# IR4427.net
KiCad netlist of a schematic drawn in EAGLE
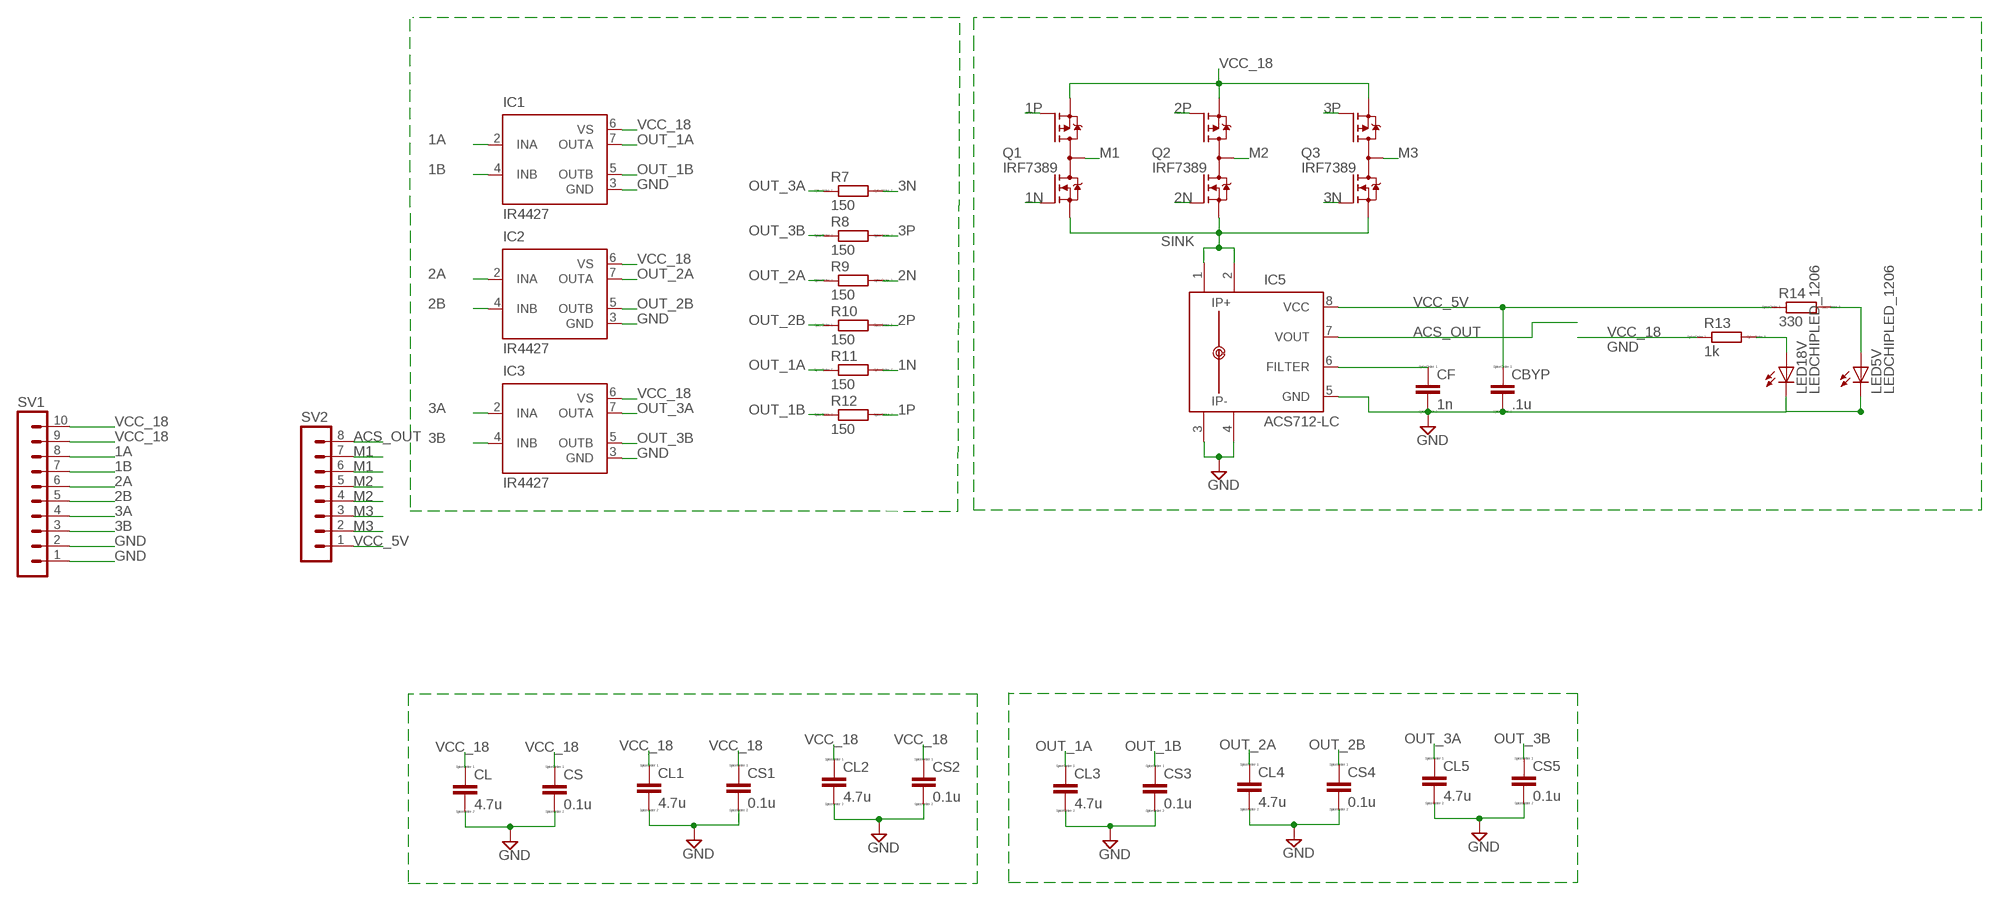
[diagram p0: schematic, sheet 1]

(export (version "E")
  (design (tool "Eeschema 10.0.6"))
  (components
    (comp (ref "CBYP")
      (value ".1u")
      (footprint "eagle-import:C1206")
      (libsource (lib "eagle-import") (part "CC1206"))
    )
    (comp (ref "CF")
      (value "1n")
      (footprint "eagle-import:C1206")
      (libsource (lib "eagle-import") (part "CC1206"))
    )
    (comp (ref "CL")
      (value "4.7u")
      (footprint "eagle-import:C1206")
      (libsource (lib "eagle-import") (part "CC1206"))
    )
    (comp (ref "CL1")
      (value "4.7u")
      (footprint "eagle-import:C1206")
      (libsource (lib "eagle-import") (part "CC1206"))
    )
    (comp (ref "CL2")
      (value "4.7u")
      (footprint "eagle-import:C1206")
      (libsource (lib "eagle-import") (part "CC1206"))
    )
    (comp (ref "CL3")
      (value "4.7u")
      (footprint "eagle-import:C1206")
      (libsource (lib "eagle-import") (part "CC1206"))
    )
    (comp (ref "CL4")
      (value "4.7u")
      (footprint "eagle-import:C1206")
      (libsource (lib "eagle-import") (part "CC1206"))
    )
    (comp (ref "CL5")
      (value "4.7u")
      (footprint "eagle-import:C1206")
      (libsource (lib "eagle-import") (part "CC1206"))
    )
    (comp (ref "CS")
      (value "0.1u")
      (footprint "eagle-import:C1206")
      (libsource (lib "eagle-import") (part "CC1206"))
    )
    (comp (ref "CS1")
      (value "0.1u")
      (footprint "eagle-import:C1206")
      (libsource (lib "eagle-import") (part "CC1206"))
    )
    (comp (ref "CS2")
      (value "0.1u")
      (footprint "eagle-import:C1206")
      (libsource (lib "eagle-import") (part "CC1206"))
    )
    (comp (ref "CS3")
      (value "0.1u")
      (footprint "eagle-import:C1206")
      (libsource (lib "eagle-import") (part "CC1206"))
    )
    (comp (ref "CS4")
      (value "0.1u")
      (footprint "eagle-import:C1206")
      (libsource (lib "eagle-import") (part "CC1206"))
    )
    (comp (ref "CS5")
      (value "0.1u")
      (footprint "eagle-import:C1206")
      (libsource (lib "eagle-import") (part "CC1206"))
    )
    (comp (ref "IC1")
      (value "IR4427")
      (footprint "eagle-import:DIL08")
      (fields (field (name "MF") "INTERNATIONAL RECTIFIER(IR)"))
      (libsource (lib "eagle-import") (part "IR4427"))
    )
    (comp (ref "IC2")
      (value "IR4427")
      (footprint "eagle-import:DIL08")
      (fields (field (name "MF") "INTERNATIONAL RECTIFIER(IR)"))
      (libsource (lib "eagle-import") (part "IR4427"))
    )
    (comp (ref "IC3")
      (value "IR4427")
      (footprint "eagle-import:DIL08")
      (fields (field (name "MF") "INTERNATIONAL RECTIFIER(IR)"))
      (libsource (lib "eagle-import") (part "IR4427"))
    )
    (comp (ref "IC5")
      (value "ACS712-LC")
      (footprint "eagle-import:SOIC8")
      (libsource (lib "eagle-import") (part "ACS712-LC"))
    )
    (comp (ref "LED5V")
      (value "LEDCHIPLED_1206")
      (footprint "eagle-import:CHIPLED_1206")
      (libsource (lib "eagle-import") (part "LEDCHIPLED_1206"))
    )
    (comp (ref "LED18V")
      (value "LEDCHIPLED_1206")
      (footprint "eagle-import:CHIPLED_1206")
      (libsource (lib "eagle-import") (part "LEDCHIPLED_1206"))
    )
    (comp (ref "Q1")
      (value "IRF7389")
      (footprint "eagle-import:SO08-IRF")
      (libsource (lib "eagle-import") (part "IRF7389"))
    )
    (comp (ref "Q2")
      (value "IRF7389")
      (footprint "eagle-import:SO08-IRF")
      (libsource (lib "eagle-import") (part "IRF7389"))
    )
    (comp (ref "Q3")
      (value "IRF7389")
      (footprint "eagle-import:SO08-IRF")
      (libsource (lib "eagle-import") (part "IRF7389"))
    )
    (comp (ref "R7")
      (value "150")
      (footprint "eagle-import:R1206")
      (libsource (lib "eagle-import") (part "RR1206"))
    )
    (comp (ref "R8")
      (value "150")
      (footprint "eagle-import:R1206")
      (libsource (lib "eagle-import") (part "RR1206"))
    )
    (comp (ref "R9")
      (value "150")
      (footprint "eagle-import:R1206")
      (libsource (lib "eagle-import") (part "RR1206"))
    )
    (comp (ref "R10")
      (value "150")
      (footprint "eagle-import:R1206")
      (libsource (lib "eagle-import") (part "RR1206"))
    )
    (comp (ref "R11")
      (value "150")
      (footprint "eagle-import:R1206")
      (libsource (lib "eagle-import") (part "RR1206"))
    )
    (comp (ref "R12")
      (value "150")
      (footprint "eagle-import:R1206")
      (libsource (lib "eagle-import") (part "RR1206"))
    )
    (comp (ref "R13")
      (value "1k")
      (footprint "eagle-import:R1206")
      (libsource (lib "eagle-import") (part "RR1206"))
    )
    (comp (ref "R14")
      (value "330")
      (footprint "eagle-import:R1206")
      (libsource (lib "eagle-import") (part "RR1206"))
    )
    (comp (ref "SV1")
      (value "MA10-1")
      (footprint "eagle-import:MA10-1")
      (libsource (lib "eagle-import") (part "MA10-1"))
    )
    (comp (ref "SV2")
      (value "MA08-1")
      (footprint "eagle-import:MA08-1")
      (libsource (lib "eagle-import") (part "MA08-1"))
    )
  )
  (nets
    (net (code "1") (name "/1A") (class "Default")
      (node (ref "IC1") (pin "2") (pinfunction "INA_2") (pintype "input"))
      (node (ref "SV1") (pin "8") (pinfunction "8_8") (pintype "passive"))
    )
    (net (code "2") (name "/1B") (class "Default")
      (node (ref "IC1") (pin "4") (pinfunction "INB_4") (pintype "input"))
      (node (ref "SV1") (pin "7") (pinfunction "7_7") (pintype "passive"))
    )
    (net (code "3") (name "/1N") (class "Default")
      (node (ref "Q1") (pin "2") (pinfunction "N-G_2") (pintype "passive"))
      (node (ref "R11") (pin "2") (pinfunction "2_2") (pintype "passive"))
    )
    (net (code "4") (name "/1P") (class "Default")
      (node (ref "Q1") (pin "4") (pinfunction "P-G_4") (pintype "passive"))
      (node (ref "R12") (pin "2") (pinfunction "2_2") (pintype "passive"))
    )
    (net (code "5") (name "/2A") (class "Default")
      (node (ref "IC2") (pin "2") (pinfunction "INA_2") (pintype "input"))
      (node (ref "SV1") (pin "6") (pinfunction "6_6") (pintype "passive"))
    )
    (net (code "6") (name "/2B") (class "Default")
      (node (ref "IC2") (pin "4") (pinfunction "INB_4") (pintype "input"))
      (node (ref "SV1") (pin "5") (pinfunction "5_5") (pintype "passive"))
    )
    (net (code "7") (name "/2N") (class "Default")
      (node (ref "Q2") (pin "2") (pinfunction "N-G_2") (pintype "passive"))
      (node (ref "R9") (pin "2") (pinfunction "2_2") (pintype "passive"))
    )
    (net (code "8") (name "/2P") (class "Default")
      (node (ref "Q2") (pin "4") (pinfunction "P-G_4") (pintype "passive"))
      (node (ref "R10") (pin "2") (pinfunction "2_2") (pintype "passive"))
    )
    (net (code "9") (name "/3A") (class "Default")
      (node (ref "IC3") (pin "2") (pinfunction "INA_2") (pintype "input"))
      (node (ref "SV1") (pin "4") (pinfunction "4_4") (pintype "passive"))
    )
    (net (code "10") (name "/3B") (class "Default")
      (node (ref "IC3") (pin "4") (pinfunction "INB_4") (pintype "input"))
      (node (ref "SV1") (pin "3") (pinfunction "3_3") (pintype "passive"))
    )
    (net (code "11") (name "/3N") (class "Default")
      (node (ref "Q3") (pin "2") (pinfunction "N-G_2") (pintype "passive"))
      (node (ref "R7") (pin "2") (pinfunction "2_2") (pintype "passive"))
    )
    (net (code "12") (name "/3P") (class "Default")
      (node (ref "Q3") (pin "4") (pinfunction "P-G_4") (pintype "passive"))
      (node (ref "R8") (pin "2") (pinfunction "2_2") (pintype "passive"))
    )
    (net (code "13") (name "/ACS_OUT") (class "Default")
      (node (ref "IC5") (pin "7") (pinfunction "VOUT_7") (pintype "output"))
      (node (ref "SV2") (pin "8") (pinfunction "8_8") (pintype "passive"))
    )
    (net (code "14") (name "/M1") (class "Default")
      (node (ref "Q1") (pin "5") (pinfunction "D_5") (pintype "passive"))
      (node (ref "Q1") (pin "6") (pinfunction "D_6") (pintype "passive"))
      (node (ref "Q1") (pin "7") (pinfunction "D_7") (pintype "passive"))
      (node (ref "Q1") (pin "8") (pinfunction "D_8") (pintype "passive"))
      (node (ref "SV2") (pin "6") (pinfunction "6_6") (pintype "passive"))
      (node (ref "SV2") (pin "7") (pinfunction "7_7") (pintype "passive"))
    )
    (net (code "15") (name "/M2") (class "Default")
      (node (ref "Q2") (pin "5") (pinfunction "D_5") (pintype "passive"))
      (node (ref "Q2") (pin "6") (pinfunction "D_6") (pintype "passive"))
      (node (ref "Q2") (pin "7") (pinfunction "D_7") (pintype "passive"))
      (node (ref "Q2") (pin "8") (pinfunction "D_8") (pintype "passive"))
      (node (ref "SV2") (pin "4") (pinfunction "4_4") (pintype "passive"))
      (node (ref "SV2") (pin "5") (pinfunction "5_5") (pintype "passive"))
    )
    (net (code "16") (name "/M3") (class "Default")
      (node (ref "Q3") (pin "5") (pinfunction "D_5") (pintype "passive"))
      (node (ref "Q3") (pin "6") (pinfunction "D_6") (pintype "passive"))
      (node (ref "Q3") (pin "7") (pinfunction "D_7") (pintype "passive"))
      (node (ref "Q3") (pin "8") (pinfunction "D_8") (pintype "passive"))
      (node (ref "SV2") (pin "2") (pinfunction "2_2") (pintype "passive"))
      (node (ref "SV2") (pin "3") (pinfunction "3_3") (pintype "passive"))
    )
    (net (code "17") (name "/OUT_1A") (class "Default")
      (node (ref "CL3") (pin "1") (pinfunction "1_1") (pintype "passive"))
      (node (ref "IC1") (pin "7") (pinfunction "OUTA_7") (pintype "output"))
      (node (ref "R11") (pin "1") (pinfunction "1_1") (pintype "passive"))
    )
    (net (code "18") (name "/OUT_1B") (class "Default")
      (node (ref "CS3") (pin "1") (pinfunction "1_1") (pintype "passive"))
      (node (ref "IC1") (pin "5") (pinfunction "OUTB_5") (pintype "output"))
      (node (ref "R12") (pin "1") (pinfunction "1_1") (pintype "passive"))
    )
    (net (code "19") (name "/OUT_2A") (class "Default")
      (node (ref "CL4") (pin "1") (pinfunction "1_1") (pintype "passive"))
      (node (ref "IC2") (pin "7") (pinfunction "OUTA_7") (pintype "output"))
      (node (ref "R9") (pin "1") (pinfunction "1_1") (pintype "passive"))
    )
    (net (code "20") (name "/OUT_2B") (class "Default")
      (node (ref "CS4") (pin "1") (pinfunction "1_1") (pintype "passive"))
      (node (ref "IC2") (pin "5") (pinfunction "OUTB_5") (pintype "output"))
      (node (ref "R10") (pin "1") (pinfunction "1_1") (pintype "passive"))
    )
    (net (code "21") (name "/OUT_3A") (class "Default")
      (node (ref "CL5") (pin "1") (pinfunction "1_1") (pintype "passive"))
      (node (ref "IC3") (pin "7") (pinfunction "OUTA_7") (pintype "output"))
      (node (ref "R7") (pin "1") (pinfunction "1_1") (pintype "passive"))
    )
    (net (code "22") (name "/OUT_3B") (class "Default")
      (node (ref "CS5") (pin "1") (pinfunction "1_1") (pintype "passive"))
      (node (ref "IC3") (pin "5") (pinfunction "OUTB_5") (pintype "output"))
      (node (ref "R8") (pin "1") (pinfunction "1_1") (pintype "passive"))
    )
    (net (code "23") (name "/SINK") (class "Default")
      (node (ref "IC5") (pin "1") (pinfunction "IP+_1") (pintype "passive"))
      (node (ref "IC5") (pin "2") (pinfunction "IP+1_2") (pintype "passive"))
      (node (ref "Q1") (pin "1") (pinfunction "N-S_1") (pintype "passive"))
      (node (ref "Q2") (pin "1") (pinfunction "N-S_1") (pintype "passive"))
      (node (ref "Q3") (pin "1") (pinfunction "N-S_1") (pintype "passive"))
    )
    (net (code "24") (name "/VCC_5V") (class "Default")
      (node (ref "CBYP") (pin "1") (pinfunction "1_1") (pintype "passive"))
      (node (ref "IC5") (pin "8") (pinfunction "VCC_8") (pintype "power_in"))
      (node (ref "R14") (pin "1") (pinfunction "1_1") (pintype "passive"))
      (node (ref "SV2") (pin "1") (pinfunction "1_1") (pintype "passive"))
    )
    (net (code "25") (name "/VCC_18") (class "Default")
      (node (ref "CL") (pin "1") (pinfunction "1_1") (pintype "passive"))
      (node (ref "CL1") (pin "1") (pinfunction "1_1") (pintype "passive"))
      (node (ref "CL2") (pin "1") (pinfunction "1_1") (pintype "passive"))
      (node (ref "CS") (pin "1") (pinfunction "1_1") (pintype "passive"))
      (node (ref "CS1") (pin "1") (pinfunction "1_1") (pintype "passive"))
      (node (ref "CS2") (pin "1") (pinfunction "1_1") (pintype "passive"))
      (node (ref "IC1") (pin "6") (pinfunction "VS_6") (pintype "power_in"))
      (node (ref "IC2") (pin "6") (pinfunction "VS_6") (pintype "power_in"))
      (node (ref "IC3") (pin "6") (pinfunction "VS_6") (pintype "power_in"))
      (node (ref "Q1") (pin "3") (pinfunction "P-S_3") (pintype "passive"))
      (node (ref "Q2") (pin "3") (pinfunction "P-S_3") (pintype "passive"))
      (node (ref "Q3") (pin "3") (pinfunction "P-S_3") (pintype "passive"))
      (node (ref "R13") (pin "1") (pinfunction "1_1") (pintype "passive"))
      (node (ref "SV1") (pin "10") (pinfunction "10_10") (pintype "passive"))
      (node (ref "SV1") (pin "9") (pinfunction "9_9") (pintype "passive"))
    )
    (net (code "26") (name "GND") (class "Default")
      (node (ref "CBYP") (pin "2") (pinfunction "2_2") (pintype "passive"))
      (node (ref "CF") (pin "2") (pinfunction "2_2") (pintype "passive"))
      (node (ref "CL") (pin "2") (pinfunction "2_2") (pintype "passive"))
      (node (ref "CL1") (pin "2") (pinfunction "2_2") (pintype "passive"))
      (node (ref "CL2") (pin "2") (pinfunction "2_2") (pintype "passive"))
      (node (ref "CL3") (pin "2") (pinfunction "2_2") (pintype "passive"))
      (node (ref "CL4") (pin "2") (pinfunction "2_2") (pintype "passive"))
      (node (ref "CL5") (pin "2") (pinfunction "2_2") (pintype "passive"))
      (node (ref "CS") (pin "2") (pinfunction "2_2") (pintype "passive"))
      (node (ref "CS1") (pin "2") (pinfunction "2_2") (pintype "passive"))
      (node (ref "CS2") (pin "2") (pinfunction "2_2") (pintype "passive"))
      (node (ref "CS3") (pin "2") (pinfunction "2_2") (pintype "passive"))
      (node (ref "CS4") (pin "2") (pinfunction "2_2") (pintype "passive"))
      (node (ref "CS5") (pin "2") (pinfunction "2_2") (pintype "passive"))
      (node (ref "IC1") (pin "3") (pinfunction "GND_3") (pintype "power_in"))
      (node (ref "IC2") (pin "3") (pinfunction "GND_3") (pintype "power_in"))
      (node (ref "IC3") (pin "3") (pinfunction "GND_3") (pintype "power_in"))
      (node (ref "IC5") (pin "3") (pinfunction "IP-_3") (pintype "passive"))
      (node (ref "IC5") (pin "4") (pinfunction "IP-1_4") (pintype "passive"))
      (node (ref "IC5") (pin "5") (pinfunction "GND_5") (pintype "power_in"))
      (node (ref "LED18V") (pin "C") (pinfunction "C_C") (pintype "passive"))
      (node (ref "LED5V") (pin "C") (pinfunction "C_C") (pintype "passive"))
      (node (ref "SV1") (pin "1") (pinfunction "1_1") (pintype "passive"))
      (node (ref "SV1") (pin "2") (pinfunction "2_2") (pintype "passive"))
    )
    (net (code "27") (name "Net-(IC5-FILTER)") (class "Default")
      (node (ref "CF") (pin "1") (pinfunction "1_1") (pintype "passive"))
      (node (ref "IC5") (pin "6") (pinfunction "FILTER_6") (pintype "bidirectional"))
    )
    (net (code "28") (name "Net-(LED5V-PadA)") (class "Default")
      (node (ref "LED5V") (pin "A") (pinfunction "A_A") (pintype "passive"))
      (node (ref "R14") (pin "2") (pinfunction "2_2") (pintype "passive"))
    )
    (net (code "29") (name "Net-(LED18V-PadA)") (class "Default")
      (node (ref "LED18V") (pin "A") (pinfunction "A_A") (pintype "passive"))
      (node (ref "R13") (pin "2") (pinfunction "2_2") (pintype "passive"))
    )
  )
)
